# adxl362_board.net
KiCad netlist of a schematic drawn in EAGLE
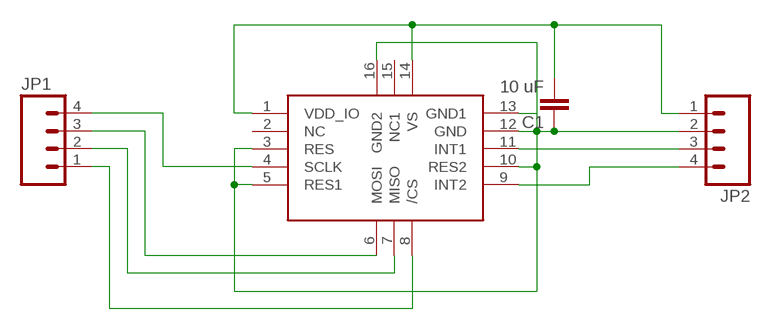
[diagram p0: schematic, sheet 1]

(export (version "E")
  (design (tool "Eeschema 10.0.6"))
  (components
    (comp (ref "C1")
      (value "10 uF")
      (footprint "eagle-import:0805")
      (libsource (lib "eagle-import") (part "CAP0805"))
    )
    (comp (ref "JP1")
      (value "M041.27MM")
      (footprint "eagle-import:1X04-1.27MM")
      (libsource (lib "eagle-import") (part "M041.27MM"))
    )
    (comp (ref "JP2")
      (value "M041.27MM")
      (footprint "eagle-import:1X04-1.27MM")
      (libsource (lib "eagle-import") (part "M041.27MM"))
    )
    (comp (ref "U$1")
      (value "ADXL362")
      (footprint "eagle-import:ADXL362_PADS")
      (libsource (lib "eagle-import") (part "ADXL362"))
    )
  )
  (nets
    (net (code "1") (name "Net-(U$1-GND)") (class "Default")
      (node (ref "C1") (pin "1") (pinfunction "1_1") (pintype "passive"))
      (node (ref "JP2") (pin "2") (pinfunction "2_2") (pintype "passive"))
      (node (ref "U$1") (pin "10") (pinfunction "RES2_10") (pintype "bidirectional"))
      (node (ref "U$1") (pin "12") (pinfunction "GND_12") (pintype "bidirectional"))
      (node (ref "U$1") (pin "13") (pinfunction "GND1_13") (pintype "bidirectional"))
      (node (ref "U$1") (pin "16") (pinfunction "GND2_16") (pintype "bidirectional"))
      (node (ref "U$1") (pin "3") (pinfunction "RES_3") (pintype "bidirectional"))
      (node (ref "U$1") (pin "5") (pinfunction "RES1_5") (pintype "bidirectional"))
    )
    (net (code "2") (name "Net-(U$1-INT1)") (class "Default")
      (node (ref "JP2") (pin "3") (pinfunction "3_3") (pintype "passive"))
      (node (ref "U$1") (pin "11") (pinfunction "INT1_11") (pintype "bidirectional"))
    )
    (net (code "3") (name "Net-(U$1-INT2)") (class "Default")
      (node (ref "JP2") (pin "4") (pinfunction "4_4") (pintype "passive"))
      (node (ref "U$1") (pin "9") (pinfunction "INT2_9") (pintype "bidirectional"))
    )
    (net (code "4") (name "Net-(U$1-MISO)") (class "Default")
      (node (ref "JP1") (pin "2") (pinfunction "2_2") (pintype "passive"))
      (node (ref "U$1") (pin "7") (pinfunction "MISO_7") (pintype "bidirectional"))
    )
    (net (code "5") (name "Net-(U$1-MOSI)") (class "Default")
      (node (ref "JP1") (pin "3") (pinfunction "3_3") (pintype "passive"))
      (node (ref "U$1") (pin "6") (pinfunction "MOSI_6") (pintype "bidirectional"))
    )
    (net (code "6") (name "Net-(U$1-SCLK)") (class "Default")
      (node (ref "JP1") (pin "4") (pinfunction "4_4") (pintype "passive"))
      (node (ref "U$1") (pin "4") (pinfunction "SCLK_4") (pintype "bidirectional"))
    )
    (net (code "7") (name "Net-(U$1-VDD_IO)") (class "Default")
      (node (ref "C1") (pin "2") (pinfunction "2_2") (pintype "passive"))
      (node (ref "JP2") (pin "1") (pinfunction "1_1") (pintype "passive"))
      (node (ref "U$1") (pin "1") (pinfunction "VDD_IO_1") (pintype "bidirectional"))
      (node (ref "U$1") (pin "14") (pinfunction "VS_14") (pintype "bidirectional"))
    )
    (net (code "8") (name "Net-(U$1-{slash}CS)") (class "Default")
      (node (ref "JP1") (pin "1") (pinfunction "1_1") (pintype "passive"))
      (node (ref "U$1") (pin "8") (pinfunction "/CS_8") (pintype "bidirectional"))
    )
    (net (code "9") (name "unconnected-(U$1-NC-Pad2)") (class "Default")
      (node (ref "U$1") (pin "2") (pinfunction "NC_2") (pintype "bidirectional"))
    )
    (net (code "10") (name "unconnected-(U$1-NC1-Pad15)") (class "Default")
      (node (ref "U$1") (pin "15") (pinfunction "NC1_15") (pintype "bidirectional"))
    )
  )
)
